# PROFIBUS_V3.net
KiCad netlist of a schematic drawn in EAGLE
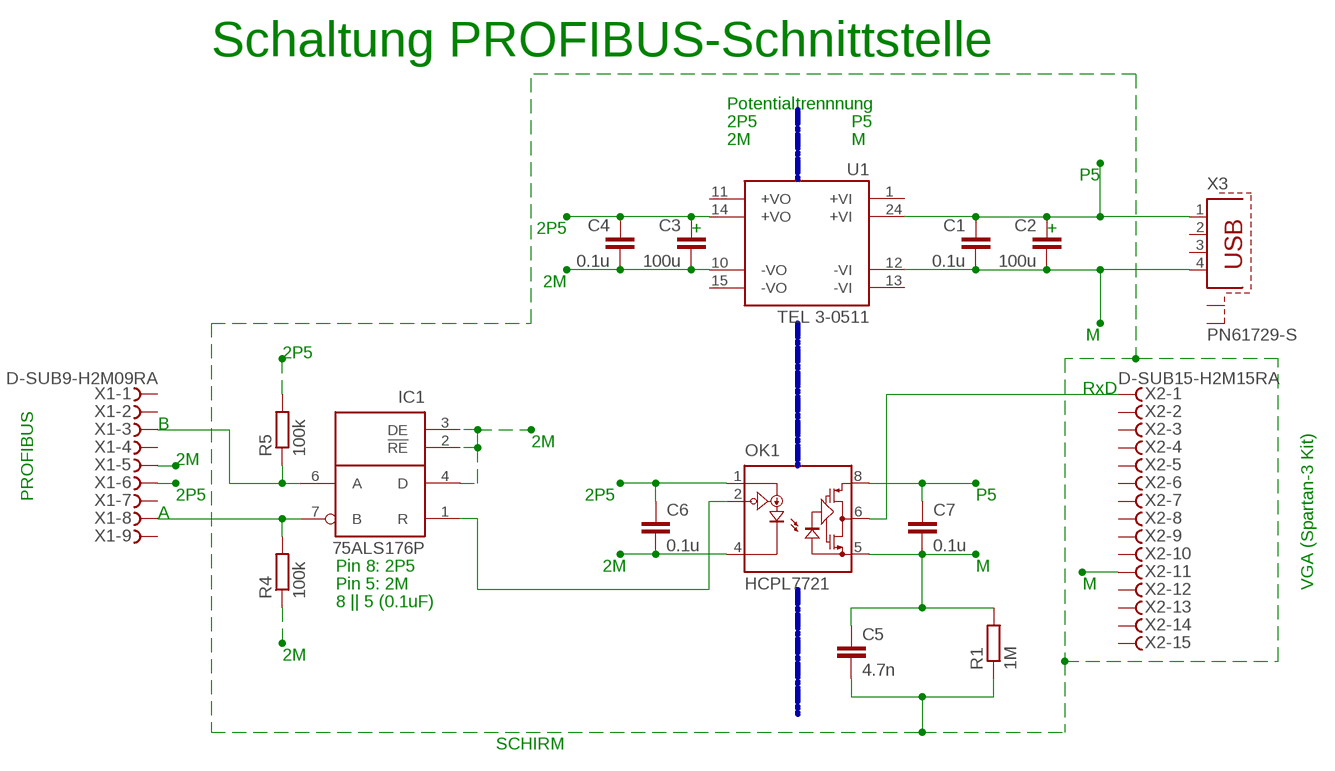
[diagram p0: schematic, sheet 1]

(export (version "E")
  (design (tool "Eeschema 10.0.6"))
  (components
    (comp (ref "C1")
      (value "0.1u")
      (footprint "eagle-import:C2.5-3")
      (libsource (lib "eagle-import") (part "C2,5-3"))
    )
    (comp (ref "C2")
      (value "100u")
      (footprint "eagle-import:C2.5-3")
      (libsource (lib "eagle-import") (part "C2,5-3"))
    )
    (comp (ref "C3")
      (value "100u")
      (footprint "eagle-import:C2.5-3")
      (libsource (lib "eagle-import") (part "C2,5-3"))
    )
    (comp (ref "C4")
      (value "0.1u")
      (footprint "eagle-import:C2.5-3")
      (libsource (lib "eagle-import") (part "C2,5-3"))
    )
    (comp (ref "C5")
      (value "4.7n")
      (footprint "eagle-import:C2.5-3")
      (libsource (lib "eagle-import") (part "C2,5-3"))
    )
    (comp (ref "C6")
      (value "0.1u")
      (footprint "eagle-import:C2.5-3")
      (libsource (lib "eagle-import") (part "C2,5-3"))
    )
    (comp (ref "C7")
      (value "0.1u")
      (footprint "eagle-import:C2.5-3")
      (libsource (lib "eagle-import") (part "C2,5-3"))
    )
    (comp (ref "IC1")
      (value "75ALS176P")
      (footprint "eagle-import:DIL08")
      (fields (field (name "MF") "TEXAS INSTRUMENTS") (field (name "MPN") "SN75ALS176P"))
      (libsource (lib "eagle-import") (part "75ALS176P"))
    )
    (comp (ref "OK1")
      (value "HCPL7721")
      (footprint "eagle-import:DIL08")
      (fields (field (name "MF") "AGILENT TECHNOLOGIES") (field (name "MPN") "HCPL-7721"))
      (libsource (lib "eagle-import") (part "HCPL7721"))
    )
    (comp (ref "R1")
      (value "1M")
      (footprint "eagle-import:0204_7")
      (libsource (lib "eagle-import") (part "R-EU_0204/7"))
    )
    (comp (ref "R4")
      (value "100k")
      (footprint "eagle-import:0204_7")
      (libsource (lib "eagle-import") (part "R-EU_0204/7"))
    )
    (comp (ref "R5")
      (value "100k")
      (footprint "eagle-import:0204_7")
      (libsource (lib "eagle-import") (part "R-EU_0204/7"))
    )
    (comp (ref "U1")
      (value "TEL 3-0511")
      (footprint "eagle-import:AM3N_DIL24")
      (libsource (lib "eagle-import") (part "AM3N-S0505"))
    )
    (comp (ref "X1")
      (value "D-SUB9-H2M09RA")
      (footprint "eagle-import:H2M09RA")
      (libsource (lib "eagle-import") (part "D-SUB9-H2M09RA"))
    )
    (comp (ref "X2")
      (value "D-SUB15-H2M15RA")
      (footprint "eagle-import:H2M15RA")
      (fields (field (name "MPN") "H2M15RA29B"))
      (libsource (lib "eagle-import") (part "D-SUB15-H2M15RA"))
    )
    (comp (ref "X3")
      (value "PN61729-S")
      (footprint "eagle-import:PN61729-S")
      (libsource (lib "eagle-import") (part "PN61729-S"))
    )
  )
  (nets
    (net (code "1") (name "/+VI") (class "Default")
      (node (ref "U1") (pin "1") (pinfunction "+VI_1") (pintype "power_in"))
    )
    (net (code "2") (name "/+VO") (class "Default")
      (node (ref "U1") (pin "11") (pinfunction "+VO_11") (pintype "power_in"))
    )
    (net (code "3") (name "/-VI") (class "Default")
      (node (ref "U1") (pin "13") (pinfunction "-VI_13") (pintype "power_in"))
    )
    (net (code "4") (name "/-VO") (class "Default")
      (node (ref "U1") (pin "15") (pinfunction "-VO_15") (pintype "power_in"))
    )
    (net (code "5") (name "Net-(C1-Pad1)") (class "Default")
      (node (ref "C1") (pin "1") (pinfunction "1_1") (pintype "passive"))
      (node (ref "C2") (pin "1") (pinfunction "1_1") (pintype "passive"))
      (node (ref "U1") (pin "24") (pinfunction "+VI_24") (pintype "power_in"))
      (node (ref "X3") (pin "1") (pinfunction "1_1") (pintype "passive"))
    )
    (net (code "6") (name "Net-(C1-Pad2)") (class "Default")
      (node (ref "C1") (pin "2") (pinfunction "2_2") (pintype "passive"))
      (node (ref "C2") (pin "2") (pinfunction "2_2") (pintype "passive"))
      (node (ref "U1") (pin "12") (pinfunction "-VI_12") (pintype "power_in"))
      (node (ref "X3") (pin "4") (pinfunction "4_4") (pintype "passive"))
    )
    (net (code "7") (name "Net-(C3-Pad1)") (class "Default")
      (node (ref "C3") (pin "1") (pinfunction "1_1") (pintype "passive"))
      (node (ref "C4") (pin "1") (pinfunction "1_1") (pintype "passive"))
      (node (ref "U1") (pin "14") (pinfunction "+VO_14") (pintype "power_in"))
    )
    (net (code "8") (name "Net-(C3-Pad2)") (class "Default")
      (node (ref "C3") (pin "2") (pinfunction "2_2") (pintype "passive"))
      (node (ref "C4") (pin "2") (pinfunction "2_2") (pintype "passive"))
      (node (ref "U1") (pin "10") (pinfunction "-VO_10") (pintype "power_in"))
    )
    (net (code "9") (name "Net-(C5-Pad2)") (class "Default")
      (node (ref "C5") (pin "2") (pinfunction "2_2") (pintype "passive"))
      (node (ref "R1") (pin "1") (pinfunction "1_1") (pintype "passive"))
    )
    (net (code "10") (name "Net-(IC1A-A)") (class "Default")
      (node (ref "IC1") (pin "6") (pinfunction "A_6") (pintype "bidirectional"))
      (node (ref "R5") (pin "1") (pinfunction "1_1") (pintype "passive"))
      (node (ref "X1") (pin "3") (pinfunction "F_3") (pintype "passive"))
    )
    (net (code "11") (name "Net-(IC1A-B)") (class "Default")
      (node (ref "IC1") (pin "7") (pinfunction "B_7") (pintype "bidirectional"))
      (node (ref "R4") (pin "2") (pinfunction "2_2") (pintype "passive"))
      (node (ref "X1") (pin "8") (pinfunction "F_8") (pintype "passive"))
    )
    (net (code "12") (name "Net-(IC1A-D)") (class "Default")
      (node (ref "IC1") (pin "2") (pinfunction "~{RE}_2") (pintype "input"))
      (node (ref "IC1") (pin "3") (pinfunction "DE_3") (pintype "input"))
      (node (ref "IC1") (pin "4") (pinfunction "D_4") (pintype "input"))
    )
    (net (code "13") (name "Net-(IC1A-R)") (class "Default")
      (node (ref "IC1") (pin "1") (pinfunction "R_1") (pintype "output"))
      (node (ref "OK1") (pin "2") (pinfunction "VI_2") (pintype "input"))
    )
    (net (code "14") (name "Net-(OK1-GND1)") (class "Default")
      (node (ref "C6") (pin "2") (pinfunction "2_2") (pintype "passive"))
      (node (ref "OK1") (pin "4") (pinfunction "GND1_4") (pintype "passive"))
    )
    (net (code "15") (name "Net-(OK1-GND2)") (class "Default")
      (node (ref "C5") (pin "1") (pinfunction "1_1") (pintype "passive"))
      (node (ref "C7") (pin "2") (pinfunction "2_2") (pintype "passive"))
      (node (ref "OK1") (pin "5") (pinfunction "GND2_5") (pintype "passive"))
      (node (ref "R1") (pin "2") (pinfunction "2_2") (pintype "passive"))
    )
    (net (code "16") (name "Net-(OK1-VDD1)") (class "Default")
      (node (ref "C6") (pin "1") (pinfunction "1_1") (pintype "passive"))
      (node (ref "OK1") (pin "1") (pinfunction "VDD1_1") (pintype "passive"))
    )
    (net (code "17") (name "Net-(OK1-VDD2)") (class "Default")
      (node (ref "C7") (pin "1") (pinfunction "1_1") (pintype "passive"))
      (node (ref "OK1") (pin "8") (pinfunction "VDD2_8") (pintype "passive"))
    )
    (net (code "18") (name "Net-(OK1-VO)") (class "Default")
      (node (ref "OK1") (pin "6") (pinfunction "VO_6") (pintype "passive"))
      (node (ref "X2") (pin "1") (pinfunction "F_1") (pintype "passive"))
    )
    (net (code "19") (name "unconnected-(R4-Pad1)") (class "Default")
      (node (ref "R4") (pin "1") (pinfunction "1_1") (pintype "passive"))
    )
    (net (code "20") (name "unconnected-(R5-Pad2)") (class "Default")
      (node (ref "R5") (pin "2") (pinfunction "2_2") (pintype "passive"))
    )
    (net (code "21") (name "unconnected-(X1A-F-Pad1)") (class "Default")
      (node (ref "X1") (pin "1") (pinfunction "F_1") (pintype "passive"))
    )
    (net (code "22") (name "unconnected-(X1B-F-Pad2)") (class "Default")
      (node (ref "X1") (pin "2") (pinfunction "F_2") (pintype "passive"))
    )
    (net (code "23") (name "unconnected-(X1D-F-Pad4)") (class "Default")
      (node (ref "X1") (pin "4") (pinfunction "F_4") (pintype "passive"))
    )
    (net (code "24") (name "unconnected-(X1E-F-Pad5)") (class "Default")
      (node (ref "X1") (pin "5") (pinfunction "F_5") (pintype "passive"))
    )
    (net (code "25") (name "unconnected-(X1F-F-Pad6)") (class "Default")
      (node (ref "X1") (pin "6") (pinfunction "F_6") (pintype "passive"))
    )
    (net (code "26") (name "unconnected-(X1G-F-Pad7)") (class "Default")
      (node (ref "X1") (pin "7") (pinfunction "F_7") (pintype "passive"))
    )
    (net (code "27") (name "unconnected-(X1I-F-Pad9)") (class "Default")
      (node (ref "X1") (pin "9") (pinfunction "F_9") (pintype "passive"))
    )
    (net (code "28") (name "unconnected-(X2B-F-Pad10)") (class "Default")
      (node (ref "X2") (pin "10") (pinfunction "F_10") (pintype "passive"))
    )
    (net (code "29") (name "unconnected-(X2C-F-Pad11)") (class "Default")
      (node (ref "X2") (pin "11") (pinfunction "F_11") (pintype "passive"))
    )
    (net (code "30") (name "unconnected-(X2D-F-Pad12)") (class "Default")
      (node (ref "X2") (pin "12") (pinfunction "F_12") (pintype "passive"))
    )
    (net (code "31") (name "unconnected-(X2E-F-Pad13)") (class "Default")
      (node (ref "X2") (pin "13") (pinfunction "F_13") (pintype "passive"))
    )
    (net (code "32") (name "unconnected-(X2F-F-Pad14)") (class "Default")
      (node (ref "X2") (pin "14") (pinfunction "F_14") (pintype "passive"))
    )
    (net (code "33") (name "unconnected-(X2G-F-Pad15)") (class "Default")
      (node (ref "X2") (pin "15") (pinfunction "F_15") (pintype "passive"))
    )
    (net (code "34") (name "unconnected-(X2H-F-Pad2)") (class "Default")
      (node (ref "X2") (pin "2") (pinfunction "F_2") (pintype "passive"))
    )
    (net (code "35") (name "unconnected-(X2I-F-Pad3)") (class "Default")
      (node (ref "X2") (pin "3") (pinfunction "F_3") (pintype "passive"))
    )
    (net (code "36") (name "unconnected-(X2J-F-Pad4)") (class "Default")
      (node (ref "X2") (pin "4") (pinfunction "F_4") (pintype "passive"))
    )
    (net (code "37") (name "unconnected-(X2K-F-Pad5)") (class "Default")
      (node (ref "X2") (pin "5") (pinfunction "F_5") (pintype "passive"))
    )
    (net (code "38") (name "unconnected-(X2L-F-Pad6)") (class "Default")
      (node (ref "X2") (pin "6") (pinfunction "F_6") (pintype "passive"))
    )
    (net (code "39") (name "unconnected-(X2M-F-Pad7)") (class "Default")
      (node (ref "X2") (pin "7") (pinfunction "F_7") (pintype "passive"))
    )
    (net (code "40") (name "unconnected-(X2N-F-Pad8)") (class "Default")
      (node (ref "X2") (pin "8") (pinfunction "F_8") (pintype "passive"))
    )
    (net (code "41") (name "unconnected-(X2O-F-Pad9)") (class "Default")
      (node (ref "X2") (pin "9") (pinfunction "F_9") (pintype "passive"))
    )
    (net (code "42") (name "unconnected-(X3-Pad2)") (class "Default")
      (node (ref "X3") (pin "2") (pinfunction "2_2") (pintype "passive"))
    )
    (net (code "43") (name "unconnected-(X3-Pad3)") (class "Default")
      (node (ref "X3") (pin "3") (pinfunction "3_3") (pintype "passive"))
    )
    (net (code "44") (name "unconnected-(X3-PadS1)") (class "Default")
      (node (ref "X3") (pin "S1") (pinfunction "S1_S1") (pintype "passive"))
    )
    (net (code "45") (name "unconnected-(X3-PadS2)") (class "Default")
      (node (ref "X3") (pin "S2") (pinfunction "S2_S2") (pintype "passive"))
    )
  )
)
